# seismometer_panelboard.net
KiCad netlist of a schematic drawn in EAGLE
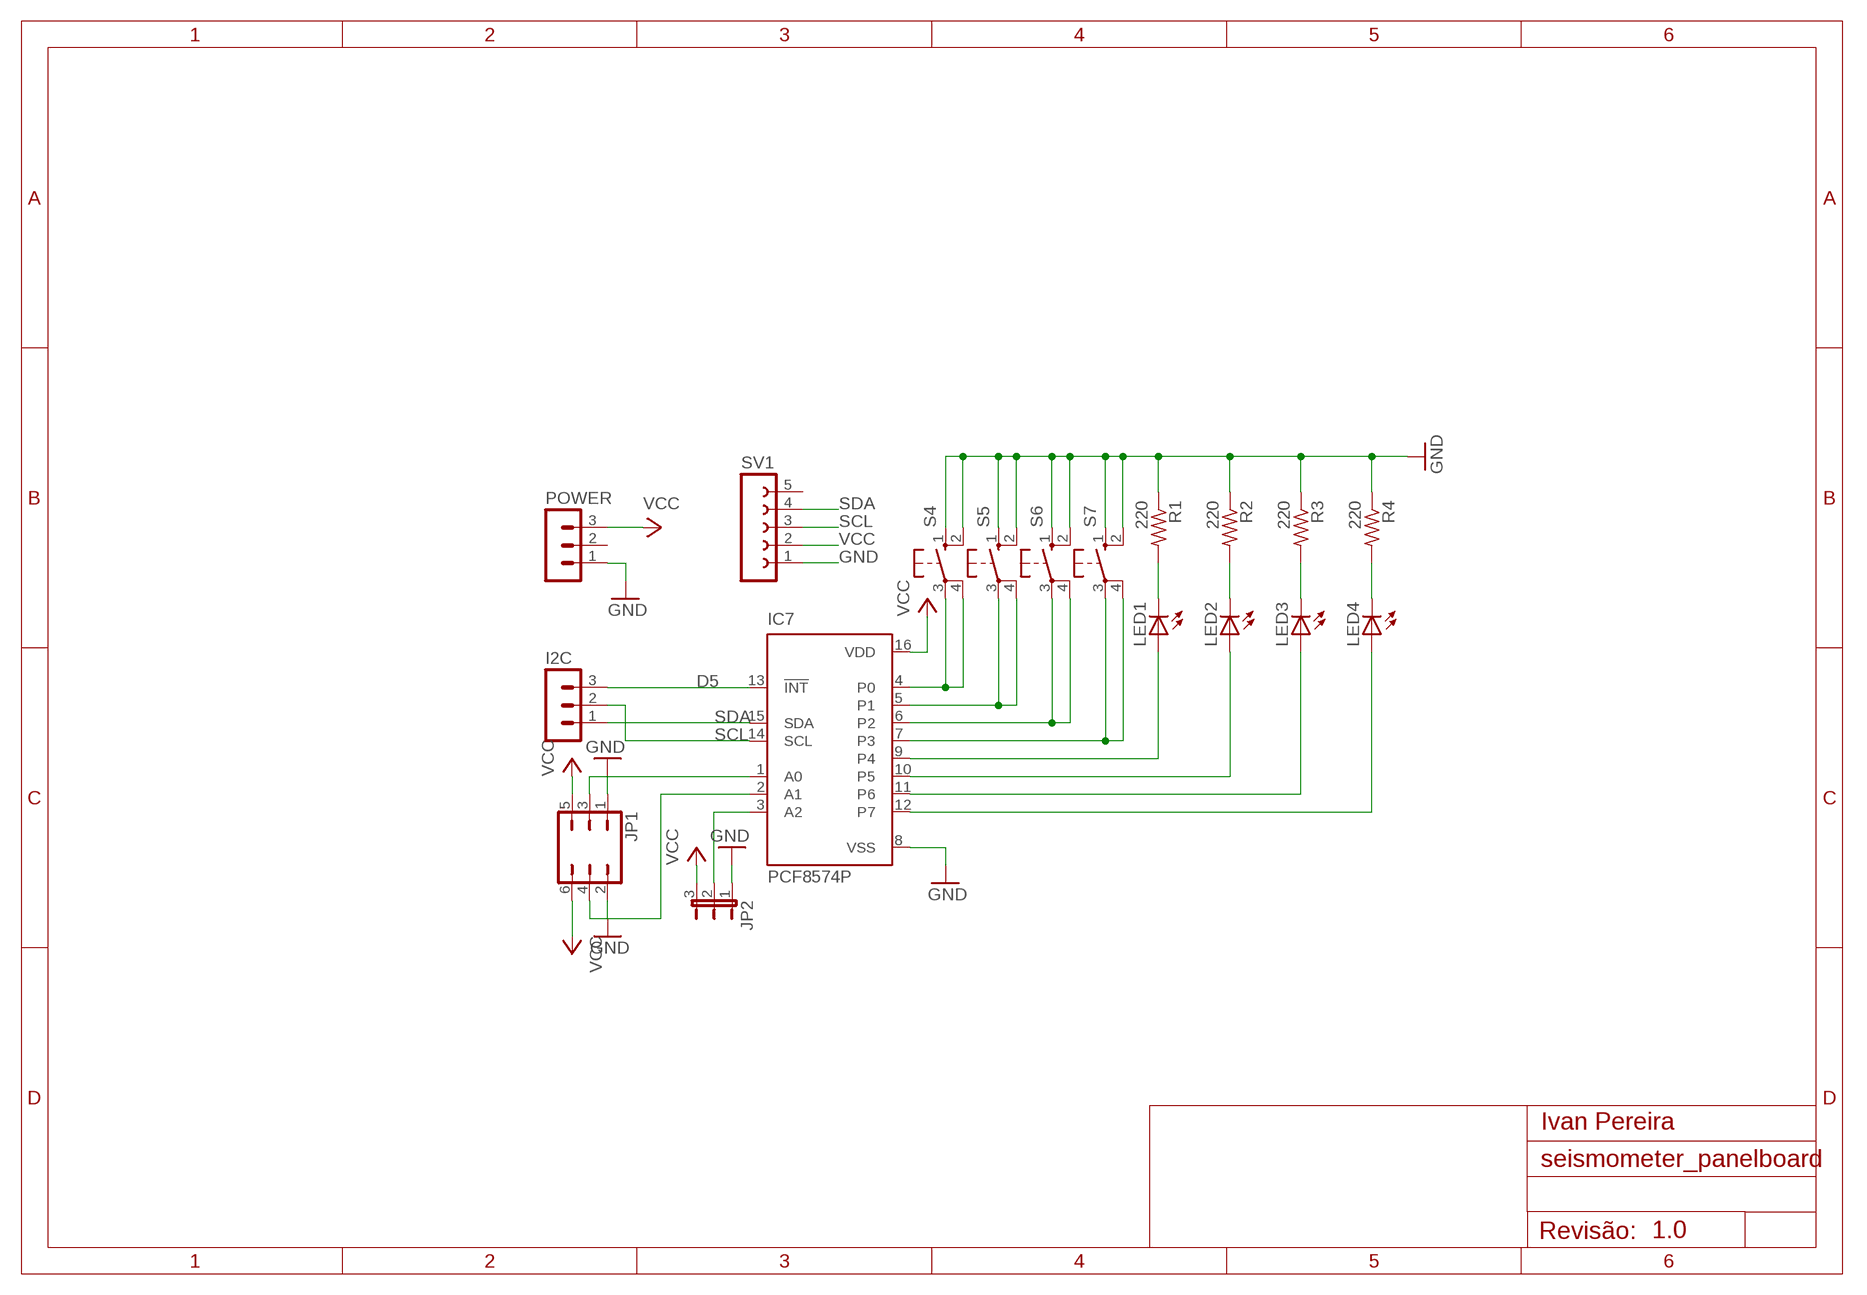
[diagram p0: schematic, sheet 1]

(export (version "E")
  (design (tool "Eeschema 10.0.6"))
  (components
    (comp (ref "I2C")
      (value "MA03-1")
      (footprint "eagle-import:MA03-1")
      (libsource (lib "eagle-import") (part "MA03-1"))
    )
    (comp (ref "IC7")
      (value "PCF8574P")
      (footprint "eagle-import:DIL16")
      (fields (field (name "MPN") "PCF8574PN"))
      (libsource (lib "eagle-import") (part "PCF8574P"))
    )
    (comp (ref "JP1")
      (value "JP3Q")
      (footprint "eagle-import:JP3Q")
      (libsource (lib "eagle-import") (part "JP3Q"))
    )
    (comp (ref "JP2")
      (value "JP2E")
      (footprint "eagle-import:JP2")
      (libsource (lib "eagle-import") (part "JP2E"))
    )
    (comp (ref "LED1")
      (value "LED3MM")
      (footprint "eagle-import:LED3MM")
      (libsource (lib "eagle-import") (part "LED3MM"))
    )
    (comp (ref "LED2")
      (value "LED3MM")
      (footprint "eagle-import:LED3MM")
      (libsource (lib "eagle-import") (part "LED3MM"))
    )
    (comp (ref "LED3")
      (value "LED3MM")
      (footprint "eagle-import:LED3MM")
      (libsource (lib "eagle-import") (part "LED3MM"))
    )
    (comp (ref "LED4")
      (value "LED3MM")
      (footprint "eagle-import:LED3MM")
      (libsource (lib "eagle-import") (part "LED3MM"))
    )
    (comp (ref "POWER")
      (value "MA03-1")
      (footprint "eagle-import:MA03-1")
      (libsource (lib "eagle-import") (part "MA03-1"))
    )
    (comp (ref "R1")
      (value "220")
      (footprint "eagle-import:0207_10")
      (libsource (lib "eagle-import") (part "R-US_0207/10"))
    )
    (comp (ref "R2")
      (value "220")
      (footprint "eagle-import:0207_10")
      (libsource (lib "eagle-import") (part "R-US_0207/10"))
    )
    (comp (ref "R3")
      (value "220")
      (footprint "eagle-import:0207_10")
      (libsource (lib "eagle-import") (part "R-US_0207/10"))
    )
    (comp (ref "R4")
      (value "220")
      (footprint "eagle-import:0207_10")
      (libsource (lib "eagle-import") (part "R-US_0207/10"))
    )
    (comp (ref "S4")
      (value "10-XX")
      (footprint "eagle-import:B3F-10XX")
      (fields (field (name "MPN") "B3F-1000"))
      (libsource (lib "eagle-import") (part "10-XX"))
    )
    (comp (ref "S5")
      (value "10-XX")
      (footprint "eagle-import:B3F-10XX")
      (fields (field (name "MPN") "B3F-1000"))
      (libsource (lib "eagle-import") (part "10-XX"))
    )
    (comp (ref "S6")
      (value "10-XX")
      (footprint "eagle-import:B3F-10XX")
      (fields (field (name "MPN") "B3F-1000"))
      (libsource (lib "eagle-import") (part "10-XX"))
    )
    (comp (ref "S7")
      (value "10-XX")
      (footprint "eagle-import:B3F-10XX")
      (fields (field (name "MPN") "B3F-1000"))
      (libsource (lib "eagle-import") (part "10-XX"))
    )
    (comp (ref "SV1")
      (value "FE05-1")
      (footprint "eagle-import:FE05-1")
      (libsource (lib "eagle-import") (part "FE05-1"))
    )
  )
  (nets
    (net (code "1") (name "/D5") (class "Default")
      (node (ref "I2C") (pin "3") (pinfunction "3_3") (pintype "passive"))
      (node (ref "IC7") (pin "13") (pinfunction "~{INT}_13") (pintype "output"))
    )
    (net (code "2") (name "/SCL") (class "Default")
      (node (ref "I2C") (pin "2") (pinfunction "2_2") (pintype "passive"))
      (node (ref "IC7") (pin "14") (pinfunction "SCL_14") (pintype "input"))
      (node (ref "SV1") (pin "3") (pinfunction "3_3") (pintype "passive"))
    )
    (net (code "3") (name "/SDA") (class "Default")
      (node (ref "I2C") (pin "1") (pinfunction "1_1") (pintype "passive"))
      (node (ref "IC7") (pin "15") (pinfunction "SDA_15") (pintype "bidirectional"))
      (node (ref "SV1") (pin "4") (pinfunction "4_4") (pintype "passive"))
    )
    (net (code "4") (name "GND") (class "Default")
      (node (ref "IC7") (pin "8") (pinfunction "VSS_8") (pintype "power_in"))
      (node (ref "JP1") (pin "1") (pinfunction "1_1") (pintype "passive"))
      (node (ref "JP1") (pin "2") (pinfunction "2_2") (pintype "passive"))
      (node (ref "JP2") (pin "1") (pinfunction "1_1") (pintype "passive"))
      (node (ref "POWER") (pin "1") (pinfunction "1_1") (pintype "passive"))
      (node (ref "R1") (pin "1") (pinfunction "1_1") (pintype "passive"))
      (node (ref "R2") (pin "1") (pinfunction "1_1") (pintype "passive"))
      (node (ref "R3") (pin "1") (pinfunction "1_1") (pintype "passive"))
      (node (ref "R4") (pin "1") (pinfunction "1_1") (pintype "passive"))
      (node (ref "S4") (pin "1") (pinfunction "S_1") (pintype "passive"))
      (node (ref "S4") (pin "2") (pinfunction "S1_2") (pintype "passive"))
      (node (ref "S5") (pin "1") (pinfunction "S_1") (pintype "passive"))
      (node (ref "S5") (pin "2") (pinfunction "S1_2") (pintype "passive"))
      (node (ref "S6") (pin "1") (pinfunction "S_1") (pintype "passive"))
      (node (ref "S6") (pin "2") (pinfunction "S1_2") (pintype "passive"))
      (node (ref "S7") (pin "1") (pinfunction "S_1") (pintype "passive"))
      (node (ref "S7") (pin "2") (pinfunction "S1_2") (pintype "passive"))
      (node (ref "SV1") (pin "1") (pinfunction "1_1") (pintype "passive"))
    )
    (net (code "5") (name "Net-(IC7-A0)") (class "Default")
      (node (ref "IC7") (pin "1") (pinfunction "A0_1") (pintype "input"))
      (node (ref "JP1") (pin "3") (pinfunction "3_3") (pintype "passive"))
    )
    (net (code "6") (name "Net-(IC7-A1)") (class "Default")
      (node (ref "IC7") (pin "2") (pinfunction "A1_2") (pintype "input"))
      (node (ref "JP1") (pin "4") (pinfunction "4_4") (pintype "passive"))
    )
    (net (code "7") (name "Net-(IC7-A2)") (class "Default")
      (node (ref "IC7") (pin "3") (pinfunction "A2_3") (pintype "input"))
      (node (ref "JP2") (pin "2") (pinfunction "2_2") (pintype "passive"))
    )
    (net (code "8") (name "Net-(IC7-P0)") (class "Default")
      (node (ref "IC7") (pin "4") (pinfunction "P0_4") (pintype "bidirectional"))
      (node (ref "S4") (pin "3") (pinfunction "P_3") (pintype "passive"))
      (node (ref "S4") (pin "4") (pinfunction "P1_4") (pintype "passive"))
    )
    (net (code "9") (name "Net-(IC7-P1)") (class "Default")
      (node (ref "IC7") (pin "5") (pinfunction "P1_5") (pintype "bidirectional"))
      (node (ref "S5") (pin "3") (pinfunction "P_3") (pintype "passive"))
      (node (ref "S5") (pin "4") (pinfunction "P1_4") (pintype "passive"))
    )
    (net (code "10") (name "Net-(IC7-P2)") (class "Default")
      (node (ref "IC7") (pin "6") (pinfunction "P2_6") (pintype "bidirectional"))
      (node (ref "S6") (pin "3") (pinfunction "P_3") (pintype "passive"))
      (node (ref "S6") (pin "4") (pinfunction "P1_4") (pintype "passive"))
    )
    (net (code "11") (name "Net-(IC7-P3)") (class "Default")
      (node (ref "IC7") (pin "7") (pinfunction "P3_7") (pintype "bidirectional"))
      (node (ref "S7") (pin "3") (pinfunction "P_3") (pintype "passive"))
      (node (ref "S7") (pin "4") (pinfunction "P1_4") (pintype "passive"))
    )
    (net (code "12") (name "Net-(IC7-P4)") (class "Default")
      (node (ref "IC7") (pin "9") (pinfunction "P4_9") (pintype "bidirectional"))
      (node (ref "LED1") (pin "A") (pinfunction "A_A") (pintype "passive"))
    )
    (net (code "13") (name "Net-(IC7-P5)") (class "Default")
      (node (ref "IC7") (pin "10") (pinfunction "P5_10") (pintype "bidirectional"))
      (node (ref "LED2") (pin "A") (pinfunction "A_A") (pintype "passive"))
    )
    (net (code "14") (name "Net-(IC7-P6)") (class "Default")
      (node (ref "IC7") (pin "11") (pinfunction "P6_11") (pintype "bidirectional"))
      (node (ref "LED3") (pin "A") (pinfunction "A_A") (pintype "passive"))
    )
    (net (code "15") (name "Net-(IC7-P7)") (class "Default")
      (node (ref "IC7") (pin "12") (pinfunction "P7_12") (pintype "bidirectional"))
      (node (ref "LED4") (pin "A") (pinfunction "A_A") (pintype "passive"))
    )
    (net (code "16") (name "Net-(LED1-C)") (class "Default")
      (node (ref "LED1") (pin "K") (pinfunction "C_K") (pintype "passive"))
      (node (ref "R1") (pin "2") (pinfunction "2_2") (pintype "passive"))
    )
    (net (code "17") (name "Net-(LED2-C)") (class "Default")
      (node (ref "LED2") (pin "K") (pinfunction "C_K") (pintype "passive"))
      (node (ref "R2") (pin "2") (pinfunction "2_2") (pintype "passive"))
    )
    (net (code "18") (name "Net-(LED3-C)") (class "Default")
      (node (ref "LED3") (pin "K") (pinfunction "C_K") (pintype "passive"))
      (node (ref "R3") (pin "2") (pinfunction "2_2") (pintype "passive"))
    )
    (net (code "19") (name "Net-(LED4-C)") (class "Default")
      (node (ref "LED4") (pin "K") (pinfunction "C_K") (pintype "passive"))
      (node (ref "R4") (pin "2") (pinfunction "2_2") (pintype "passive"))
    )
    (net (code "20") (name "VCC") (class "Default")
      (node (ref "IC7") (pin "16") (pinfunction "VDD_16") (pintype "power_in"))
      (node (ref "JP1") (pin "5") (pinfunction "5_5") (pintype "passive"))
      (node (ref "JP1") (pin "6") (pinfunction "6_6") (pintype "passive"))
      (node (ref "JP2") (pin "3") (pinfunction "3_3") (pintype "passive"))
      (node (ref "POWER") (pin "3") (pinfunction "3_3") (pintype "passive"))
      (node (ref "SV1") (pin "2") (pinfunction "2_2") (pintype "passive"))
    )
    (net (code "21") (name "unconnected-(POWER-Pad2)") (class "Default")
      (node (ref "POWER") (pin "2") (pinfunction "2_2") (pintype "passive"))
    )
    (net (code "22") (name "unconnected-(SV1-Pad5)") (class "Default")
      (node (ref "SV1") (pin "5") (pinfunction "5_5") (pintype "passive"))
    )
  )
)
